# hbridge.net
KiCad netlist of a schematic drawn in EAGLE
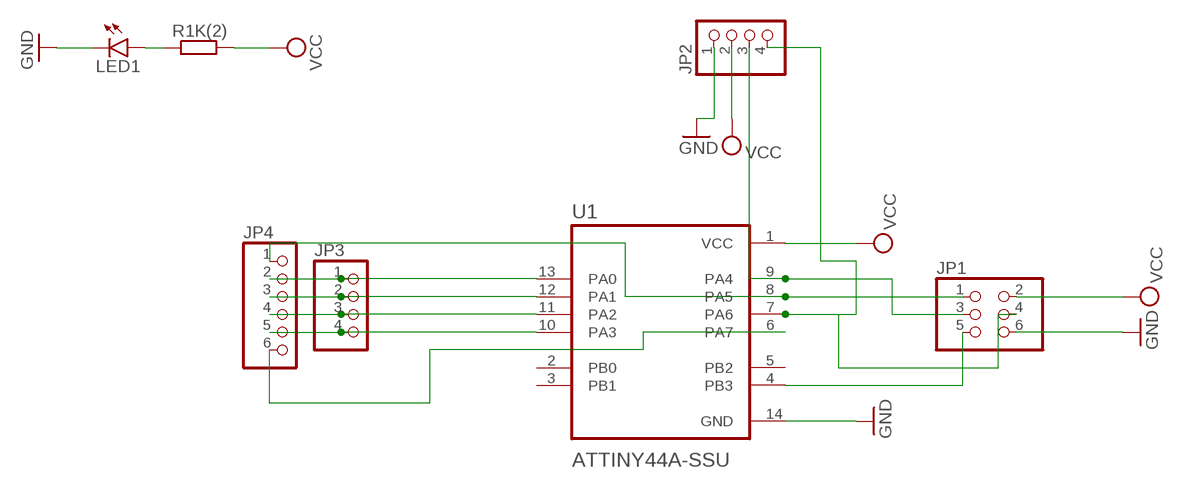
[diagram p0: schematic, sheet 1]

(export (version "E")
  (design (tool "Eeschema 10.0.6"))
  (components
    (comp (ref "JP1")
      (value "PINHD-2X03_2.54-SMD")
      (footprint "eagle-import:2X03SMD")
      (libsource (lib "eagle-import") (part "PINHD-2X03_2.54-SMD"))
    )
    (comp (ref "JP2")
      (value "PINHD-1X04_2.54-SMD")
      (footprint "eagle-import:1X04SMD")
      (libsource (lib "eagle-import") (part "PINHD-1X04_2.54-SMD"))
    )
    (comp (ref "JP3")
      (value "PINHD-1X4")
      (footprint "eagle-import:1X04")
      (libsource (lib "eagle-import") (part "PINHD-1X4"))
    )
    (comp (ref "JP4")
      (value "PINHD-1X6")
      (footprint "eagle-import:1X06")
      (libsource (lib "eagle-import") (part "PINHD-1X6"))
    )
    (comp (ref "LED1")
      (value "LEDCHIPLED_1206")
      (footprint "eagle-import:CHIPLED_1206")
      (libsource (lib "eagle-import") (part "LEDCHIPLED_1206"))
    )
    (comp (ref "R1K(2)")
      (value "R-EU_R1206")
      (footprint "eagle-import:R1206")
      (libsource (lib "eagle-import") (part "R-EU_R1206"))
    )
    (comp (ref "U1")
      (value "ATTINY44A-SSU")
      (footprint "eagle-import:SOIC127P600X175-14N")
      (fields (field (name "MF") "Microchip"))
      (libsource (lib "eagle-import") (part "ATTINY44A-SSU"))
    )
  )
  (nets
    (net (code "1") (name "GND") (class "Default")
      (node (ref "JP1") (pin "6") (pinfunction "6_6") (pintype "passive"))
      (node (ref "JP2") (pin "1") (pinfunction "1_1") (pintype "passive"))
      (node (ref "LED1") (pin "C") (pinfunction "C_C") (pintype "passive"))
      (node (ref "U1") (pin "14") (pinfunction "GND_14") (pintype "power_in"))
    )
    (net (code "2") (name "Net-(LED1-PadA)") (class "Default")
      (node (ref "LED1") (pin "A") (pinfunction "A_A") (pintype "passive"))
      (node (ref "R1K(2)") (pin "1") (pinfunction "1_1") (pintype "passive"))
    )
    (net (code "3") (name "Net-(U1-PA0)") (class "Default")
      (node (ref "JP3") (pin "1") (pinfunction "1_1") (pintype "passive"))
      (node (ref "JP4") (pin "2") (pinfunction "2_2") (pintype "passive"))
      (node (ref "U1") (pin "13") (pinfunction "PA0_13") (pintype "bidirectional"))
    )
    (net (code "4") (name "Net-(U1-PA1)") (class "Default")
      (node (ref "JP3") (pin "2") (pinfunction "2_2") (pintype "passive"))
      (node (ref "JP4") (pin "3") (pinfunction "3_3") (pintype "passive"))
      (node (ref "U1") (pin "12") (pinfunction "PA1_12") (pintype "bidirectional"))
    )
    (net (code "5") (name "Net-(U1-PA2)") (class "Default")
      (node (ref "JP3") (pin "3") (pinfunction "3_3") (pintype "passive"))
      (node (ref "JP4") (pin "4") (pinfunction "4_4") (pintype "passive"))
      (node (ref "U1") (pin "11") (pinfunction "PA2_11") (pintype "bidirectional"))
    )
    (net (code "6") (name "Net-(U1-PA3)") (class "Default")
      (node (ref "JP3") (pin "4") (pinfunction "4_4") (pintype "passive"))
      (node (ref "JP4") (pin "5") (pinfunction "5_5") (pintype "passive"))
      (node (ref "U1") (pin "10") (pinfunction "PA3_10") (pintype "bidirectional"))
    )
    (net (code "7") (name "Net-(U1-PA4)") (class "Default")
      (node (ref "JP1") (pin "3") (pinfunction "3_3") (pintype "passive"))
      (node (ref "JP2") (pin "3") (pinfunction "3_3") (pintype "passive"))
      (node (ref "U1") (pin "9") (pinfunction "PA4_9") (pintype "bidirectional"))
    )
    (net (code "8") (name "Net-(U1-PA5)") (class "Default")
      (node (ref "JP1") (pin "1") (pinfunction "1_1") (pintype "passive"))
      (node (ref "JP4") (pin "1") (pinfunction "1_1") (pintype "passive"))
      (node (ref "U1") (pin "8") (pinfunction "PA5_8") (pintype "bidirectional"))
    )
    (net (code "9") (name "Net-(U1-PA6)") (class "Default")
      (node (ref "JP1") (pin "4") (pinfunction "4_4") (pintype "passive"))
      (node (ref "JP2") (pin "4") (pinfunction "4_4") (pintype "passive"))
      (node (ref "U1") (pin "7") (pinfunction "PA6_7") (pintype "bidirectional"))
    )
    (net (code "10") (name "Net-(U1-PA7)") (class "Default")
      (node (ref "JP4") (pin "6") (pinfunction "6_6") (pintype "passive"))
      (node (ref "U1") (pin "6") (pinfunction "PA7_6") (pintype "bidirectional"))
    )
    (net (code "11") (name "Net-(U1-PB3)") (class "Default")
      (node (ref "JP1") (pin "5") (pinfunction "5_5") (pintype "passive"))
      (node (ref "U1") (pin "4") (pinfunction "PB3_4") (pintype "bidirectional"))
    )
    (net (code "12") (name "VCC") (class "Default")
      (node (ref "JP1") (pin "2") (pinfunction "2_2") (pintype "passive"))
      (node (ref "JP2") (pin "2") (pinfunction "2_2") (pintype "passive"))
      (node (ref "R1K(2)") (pin "2") (pinfunction "2_2") (pintype "passive"))
      (node (ref "U1") (pin "1") (pinfunction "VCC_1") (pintype "power_in"))
    )
    (net (code "13") (name "unconnected-(U1-PB0-Pad2)") (class "Default")
      (node (ref "U1") (pin "2") (pinfunction "PB0_2") (pintype "bidirectional"))
    )
    (net (code "14") (name "unconnected-(U1-PB1-Pad3)") (class "Default")
      (node (ref "U1") (pin "3") (pinfunction "PB1_3") (pintype "bidirectional"))
    )
    (net (code "15") (name "unconnected-(U1-PB2-Pad5)") (class "Default")
      (node (ref "U1") (pin "5") (pinfunction "PB2_5") (pintype "bidirectional"))
    )
  )
)
